# 06-_MCU_PORTA_B.net
KiCad netlist of a schematic drawn in Altium Designer
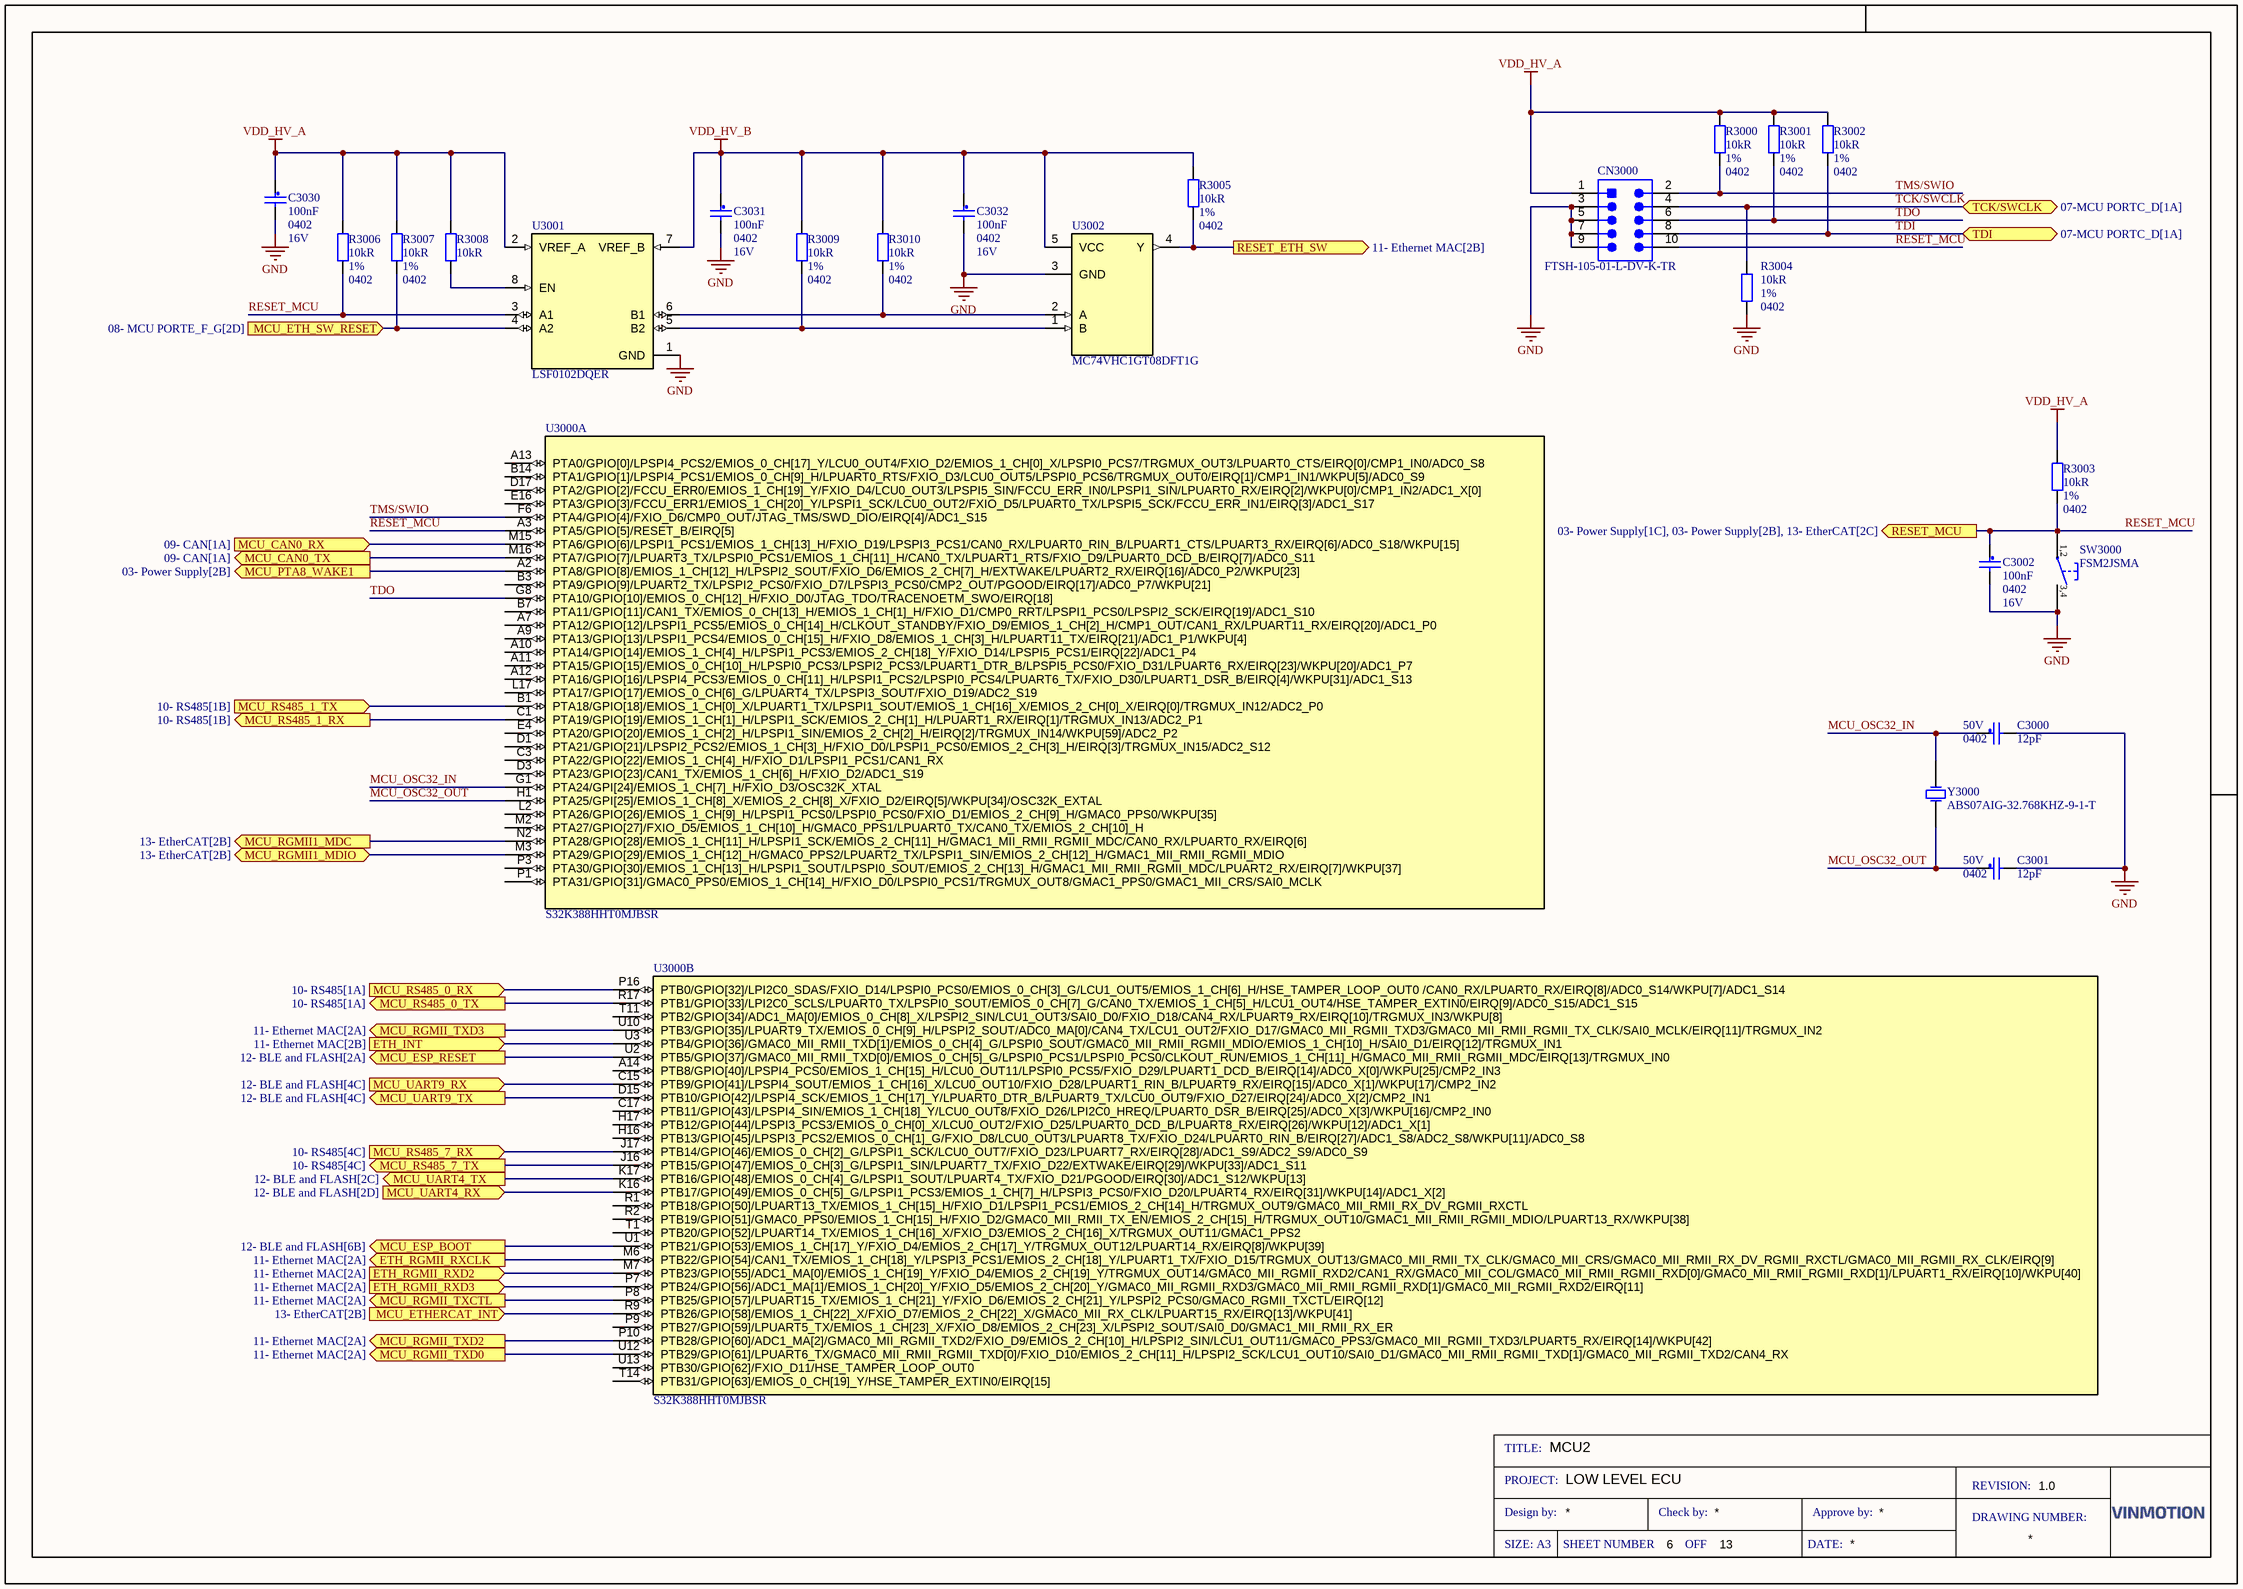
[diagram p0: 06- MCU PORTA_B.SchDoc]

(export (version "E")
  (design (tool "Eeschema 10.0.6"))
  (components
    (comp (ref "C3000")
      (value "GCM1555C1H120JA16D")
      (footprint "CAP0402")
      (description "CAP CER 12PF 50V C0G/NP0 0402")
      (fields
        (field (name "TOLERANCE") "5%")
        (field (name "VOLTAGE RATING") "50V")
        (field (name "CASE/PACKAGE") "0402")
        (field (name "CAPACITANCE") "12pF")
      )
      (libsource (lib "VMO_Lib") (part "CMP-00203-1"))
    )
    (comp (ref "C3001")
      (value "GCM1555C1H120JA16D")
      (footprint "CAP0402")
      (description "CAP CER 12PF 50V C0G/NP0 0402")
      (fields
        (field (name "TOLERANCE") "5%")
        (field (name "VOLTAGE RATING") "50V")
        (field (name "CASE/PACKAGE") "0402")
        (field (name "CAPACITANCE") "12pF")
      )
      (libsource (lib "VMO_Lib") (part "CMP-00203-1"))
    )
    (comp (ref "C3002")
      (value "0402YC104KAT2A")
      (footprint "CAP0402")
      (description "CAP CER 0.1UF 16V X7R 0402")
      (fields
        (field (name "CAPACITANCE") "100nF")
        (field (name "CASE/PACKAGE") "0402")
        (field (name "VOLTAGE RATING (DC)") "16V")
      )
      (libsource (lib "VMO_Lib") (part "CMP-00988-1"))
    )
    (comp (ref "C3030")
      (value "0402YC104KAT2A")
      (footprint "CAP0402")
      (description "CAP CER 0.1UF 16V X7R 0402")
      (fields
        (field (name "CAPACITANCE") "100nF")
        (field (name "CASE/PACKAGE") "0402")
        (field (name "VOLTAGE RATING (DC)") "16V")
      )
      (libsource (lib "VMO_Lib") (part "CMP-00988-1"))
    )
    (comp (ref "C3031")
      (value "0402YC104KAT2A")
      (footprint "CAP0402")
      (description "CAP CER 0.1UF 16V X7R 0402")
      (fields
        (field (name "CAPACITANCE") "100nF")
        (field (name "CASE/PACKAGE") "0402")
        (field (name "VOLTAGE RATING (DC)") "16V")
      )
      (libsource (lib "VMO_Lib") (part "CMP-00988-1"))
    )
    (comp (ref "C3032")
      (value "0402YC104KAT2A")
      (footprint "CAP0402")
      (description "CAP CER 0.1UF 16V X7R 0402")
      (fields
        (field (name "CAPACITANCE") "100nF")
        (field (name "CASE/PACKAGE") "0402")
        (field (name "VOLTAGE RATING (DC)") "16V")
      )
      (libsource (lib "VMO_Lib") (part "CMP-00988-1"))
    )
    (comp (ref "CN3000")
      (value "FTSH-105-01-L-DV-K-TR")
      (footprint "SMTC-FTSH-105-01-L-DV-K_R")
      (description "CONN HEADER SMD 10POS 1.27MM")
      (libsource (lib "VMO_Lib") (part "CMP-ROOT-0060-2"))
    )
    (comp (ref "R3000")
      (value "10kR")
      (footprint "RES0402")
      (description "RES 10K OHM 1% 1/16W 0402")
      (fields
        (field (name "MANUFACTURER") "Stackpole Electronics")
        (field (name "MANUFACTURER PART NUMBER") "RMCF0402FT10K0")
        (field (name "TOLERANCE") "1%")
        (field (name "CASE/PACKAGE") "0402")
      )
      (libsource (lib "VMO_Lib") (part "CMP-01105-1"))
    )
    (comp (ref "R3001")
      (value "10kR")
      (footprint "RES0402")
      (description "RES 10K OHM 1% 1/16W 0402")
      (fields
        (field (name "MANUFACTURER") "Stackpole Electronics")
        (field (name "MANUFACTURER PART NUMBER") "RMCF0402FT10K0")
        (field (name "TOLERANCE") "1%")
        (field (name "CASE/PACKAGE") "0402")
      )
      (libsource (lib "VMO_Lib") (part "CMP-01105-1"))
    )
    (comp (ref "R3002")
      (value "10kR")
      (footprint "RES0402")
      (description "RES 10K OHM 1% 1/16W 0402")
      (fields
        (field (name "MANUFACTURER") "Stackpole Electronics")
        (field (name "MANUFACTURER PART NUMBER") "RMCF0402FT10K0")
        (field (name "TOLERANCE") "1%")
        (field (name "CASE/PACKAGE") "0402")
      )
      (libsource (lib "VMO_Lib") (part "CMP-01105-1"))
    )
    (comp (ref "R3003")
      (value "10kR")
      (footprint "RES0402")
      (description "RES 10K OHM 1% 1/16W 0402")
      (fields
        (field (name "MANUFACTURER") "Stackpole Electronics")
        (field (name "MANUFACTURER PART NUMBER") "RMCF0402FT10K0")
        (field (name "TOLERANCE") "1%")
        (field (name "CASE/PACKAGE") "0402")
      )
      (libsource (lib "VMO_Lib") (part "CMP-01105-1"))
    )
    (comp (ref "R3004")
      (value "10kR")
      (footprint "RES0402")
      (description "RES 10K OHM 1% 1/16W 0402")
      (fields
        (field (name "MANUFACTURER") "Stackpole Electronics")
        (field (name "MANUFACTURER PART NUMBER") "RMCF0402FT10K0")
        (field (name "TOLERANCE") "1%")
        (field (name "CASE/PACKAGE") "0402")
      )
      (libsource (lib "VMO_Lib") (part "CMP-01105-1"))
    )
    (comp (ref "R3005")
      (value "10kR")
      (footprint "RES0402")
      (description "RES 10K OHM 1% 1/16W 0402")
      (fields
        (field (name "MANUFACTURER") "Stackpole Electronics")
        (field (name "MANUFACTURER PART NUMBER") "RMCF0402FT10K0")
        (field (name "TOLERANCE") "1%")
        (field (name "CASE/PACKAGE") "0402")
      )
      (libsource (lib "VMO_Lib") (part "CMP-01105-1"))
    )
    (comp (ref "R3006")
      (value "10kR")
      (footprint "RES0402")
      (description "RES 10K OHM 1% 1/16W 0402")
      (fields
        (field (name "MANUFACTURER") "Stackpole Electronics")
        (field (name "MANUFACTURER PART NUMBER") "RMCF0402FT10K0")
        (field (name "TOLERANCE") "1%")
        (field (name "CASE/PACKAGE") "0402")
      )
      (libsource (lib "VMO_Lib") (part "CMP-01105-1"))
    )
    (comp (ref "R3007")
      (value "10kR")
      (footprint "RES0402")
      (description "RES 10K OHM 1% 1/16W 0402")
      (fields
        (field (name "MANUFACTURER") "Stackpole Electronics")
        (field (name "MANUFACTURER PART NUMBER") "RMCF0402FT10K0")
        (field (name "TOLERANCE") "1%")
        (field (name "CASE/PACKAGE") "0402")
      )
      (libsource (lib "VMO_Lib") (part "CMP-01105-1"))
    )
    (comp (ref "R3008")
      (value "10kR")
      (footprint "RES0402")
      (description "RES 10K OHM 1% 1/16W 0402")
      (fields
        (field (name "MANUFACTURER") "Stackpole Electronics")
        (field (name "MANUFACTURER PART NUMBER") "RMCF0402FT10K0")
      )
      (libsource (lib "VMO_Lib") (part "CMP-01105-1"))
    )
    (comp (ref "R3009")
      (value "10kR")
      (footprint "RES0402")
      (description "RES 10K OHM 1% 1/16W 0402")
      (fields
        (field (name "MANUFACTURER") "Stackpole Electronics")
        (field (name "MANUFACTURER PART NUMBER") "RMCF0402FT10K0")
        (field (name "TOLERANCE") "1%")
        (field (name "CASE/PACKAGE") "0402")
      )
      (libsource (lib "VMO_Lib") (part "CMP-01105-1"))
    )
    (comp (ref "R3010")
      (value "10kR")
      (footprint "RES0402")
      (description "RES 10K OHM 1% 1/16W 0402")
      (fields
        (field (name "MANUFACTURER") "Stackpole Electronics")
        (field (name "MANUFACTURER PART NUMBER") "RMCF0402FT10K0")
        (field (name "TOLERANCE") "1%")
        (field (name "CASE/PACKAGE") "0402")
      )
      (libsource (lib "VMO_Lib") (part "CMP-01105-1"))
    )
    (comp (ref "SW3000")
      (value "FSM2JSMA")
      (footprint "TE_FSM2JSMASTR_R")
      (description "SWITCH TACTILE SPST-NO 0.05A 24V")
      (libsource (lib "VMO_Lib") (part "CMP-ROOT-0128-12"))
    )
    (comp (ref "U3000")
      (value "S32K388HHT0MJBSR")
      (footprint "BGA289C80P17X17_1400X1400X152")
      (fields (field (name "MANUFACTURER") "NXP Semiconductors"))
      (libsource (lib "VMO_Lib") (part "CMP-01150-1"))
    )
    (comp (ref "U3001")
      (value "LSF0102DQER")
      (footprint "8-XFDFN")
      (description "IC VOLTAGE LEVEL BIDIR 8-X2SON")
      (fields (field (name "MANUFACTURER") "Texas Instruments"))
      (libsource (lib "VMO_Lib") (part "CMP-01193-1"))
    )
    (comp (ref "U3002")
      (value "MC74VHC1GT08DFT1G")
      (footprint "SOT95P280X145-5N")
      (description "IC GATE AND 1CH 2-INP SC88A")
      (fields (field (name "MANUFACTURER") "onsemi"))
      (libsource (lib "VMO_Lib") (part "CMP-01194-1"))
    )
    (comp (ref "Y3000")
      (value "ABS07AIG-32.768KHZ-9-1-T")
      (footprint "CRYSTAL3215")
      (description "CRYSTAL 32.768KHZ 9PF SMD")
      (libsource (lib "VMO_Lib") (part "CMP-00382-1"))
    )
  )
  (nets
    (net (code "1") (name "/ETH_INT") (class "Default")
      (node (ref "U3000") (pin "U3") (pinfunction "PTB4/GPIO[36]/GMAC0_MII_RMII_TXD[1]/EMIOS_0_CH[4]_G/LPSPI0_SOUT/GMAC0_MII_RMII_RGMII_MDIO/EMIOS_1_CH[10]_H/SAI0_D1/EIRQ[12]/TRGMUX_IN1_U3") (pintype "bidirectional"))
    )
    (net (code "2") (name "/ETH_RGMII_RXCLK") (class "Default")
      (node (ref "U3000") (pin "M6") (pinfunction "PTB22/GPIO[54]/CAN1_TX/EMIOS_1_CH[18]_Y/LPSPI3_PCS1/EMIOS_2_CH[18]_Y/LPUART1_TX/FXIO_D15/TRGMUX_OUT13/GMAC0_MII_RMII_TX_CLK/GMAC0_MII_CRS/GMAC0_MII_RMII_RX_DV_RGMII_RXCTL/GMAC0_MII_RGMII_RX_CLK/EIRQ[9]_M6") (pintype "bidirectional"))
    )
    (net (code "3") (name "/ETH_RGMII_RXD2") (class "Default")
      (node (ref "U3000") (pin "M7") (pinfunction "PTB23/GPIO[55]/ADC1_MA[0]/EMIOS_1_CH[19]_Y/FXIO_D4/EMIOS_2_CH[19]_Y/TRGMUX_OUT14/GMAC0_MII_RGMII_RXD2/CAN1_RX/GMAC0_MII_COL/GMAC0_MII_RMII_RGMII_RXD[0]/GMAC0_MII_RMII_RGMII_RXD[1]/LPUART1_RX/EIRQ[10]/WKPU[40]_M7") (pintype "bidirectional"))
    )
    (net (code "4") (name "/ETH_RGMII_RXD3") (class "Default")
      (node (ref "U3000") (pin "P7") (pinfunction "PTB24/GPIO[56]/ADC1_MA[1]/EMIOS_1_CH[20]_Y/FXIO_D5/EMIOS_2_CH[20]_Y/GMAC0_MII_RGMII_RXD3/GMAC0_MII_RMII_RGMII_RXD[1]/GMAC0_MII_RGMII_RXD2/EIRQ[11]_P7") (pintype "bidirectional"))
    )
    (net (code "5") (name "/MCU_CAN0_RX") (class "Default")
      (node (ref "U3000") (pin "M15") (pinfunction "PTA6/GPIO[6]/LPSPI1_PCS1/EMIOS_1_CH[13]_H/FXIO_D19/LPSPI3_PCS1/CAN0_RX/LPUART0_RIN_B/LPUART1_CTS/LPUART3_RX/EIRQ[6]/ADC0_S18/WKPU[15]_M15") (pintype "bidirectional"))
    )
    (net (code "6") (name "/MCU_CAN0_TX") (class "Default")
      (node (ref "U3000") (pin "M16") (pinfunction "PTA7/GPIO[7]/LPUART3_TX/LPSPI0_PCS1/EMIOS_1_CH[11]_H/CAN0_TX/LPUART1_RTS/FXIO_D9/LPUART0_DCD_B/EIRQ[7]/ADC0_S11_M16") (pintype "bidirectional"))
    )
    (net (code "7") (name "/MCU_ESP_BOOT") (class "Default")
      (node (ref "U3000") (pin "U1") (pinfunction "PTB21/GPIO[53]/EMIOS_1_CH[17]_Y/FXIO_D4/EMIOS_2_CH[17]_Y/TRGMUX_OUT12/LPUART14_RX/EIRQ[8]/WKPU[39]_U1") (pintype "bidirectional"))
    )
    (net (code "8") (name "/MCU_ESP_RESET") (class "Default")
      (node (ref "U3000") (pin "U2") (pinfunction "PTB5/GPIO[37]/GMAC0_MII_RMII_TXD[0]/EMIOS_0_CH[5]_G/LPSPI0_PCS1/LPSPI0_PCS0/CLKOUT_RUN/EMIOS_1_CH[11]_H/GMAC0_MII_RMII_RGMII_MDC/EIRQ[13]/TRGMUX_IN0_U2") (pintype "bidirectional"))
    )
    (net (code "9") (name "/MCU_ETHERCAT_INT") (class "Default")
      (node (ref "U3000") (pin "R9") (pinfunction "PTB26/GPIO[58]/EMIOS_1_CH[22]_X/FXIO_D7/EMIOS_2_CH[22]_X/GMAC0_MII_RX_CLK/LPUART15_RX/EIRQ[13]/WKPU[41]_R9") (pintype "bidirectional"))
    )
    (net (code "10") (name "/MCU_ETH_SW_RESET") (class "Default")
      (node (ref "R3007") (pin "1") (pinfunction "1_1") (pintype "passive"))
      (node (ref "U3001") (pin "4") (pinfunction "A2_4") (pintype "bidirectional"))
    )
    (net (code "11") (name "/MCU_OSC32_IN") (class "Default")
      (node (ref "C3000") (pin "1") (pinfunction "1_1") (pintype "passive"))
      (node (ref "U3000") (pin "G1") (pinfunction "PTA24/GPI[24]/EMIOS_1_CH[7]_H/FXIO_D3/OSC32K_XTAL_G1") (pintype "bidirectional"))
      (node (ref "Y3000") (pin "2") (pinfunction "OSC2_2") (pintype "passive"))
    )
    (net (code "12") (name "/MCU_OSC32_OUT") (class "Default")
      (node (ref "C3001") (pin "1") (pinfunction "1_1") (pintype "passive"))
      (node (ref "U3000") (pin "H1") (pinfunction "PTA25/GPI[25]/EMIOS_1_CH[8]_X/EMIOS_2_CH[8]_X/FXIO_D2/EIRQ[5]/WKPU[34]/OSC32K_EXTAL_H1") (pintype "bidirectional"))
      (node (ref "Y3000") (pin "1") (pinfunction "OSC1_1") (pintype "passive"))
    )
    (net (code "13") (name "/MCU_PTA8_WAKE1") (class "Default")
      (node (ref "U3000") (pin "A2") (pinfunction "PTA8/GPIO[8]/EMIOS_1_CH[12]_H/LPSPI2_SOUT/FXIO_D6/EMIOS_2_CH[7]_H/EXTWAKE/LPUART2_RX/EIRQ[16]/ADC0_P2/WKPU[23]_A2") (pintype "bidirectional"))
    )
    (net (code "14") (name "/MCU_RGMII1_MDC") (class "Default")
      (node (ref "U3000") (pin "N2") (pinfunction "PTA28/GPIO[28]/EMIOS_1_CH[11]_H/LPSPI1_SCK/EMIOS_2_CH[11]_H/GMAC1_MII_RMII_RGMII_MDC/CAN0_RX/LPUART0_RX/EIRQ[6]_N2") (pintype "bidirectional"))
    )
    (net (code "15") (name "/MCU_RGMII1_MDIO") (class "Default")
      (node (ref "U3000") (pin "M3") (pinfunction "PTA29/GPIO[29]/EMIOS_1_CH[12]_H/GMAC0_PPS2/LPUART2_TX/LPSPI1_SIN/EMIOS_2_CH[12]_H/GMAC1_MII_RMII_RGMII_MDIO_M3") (pintype "bidirectional"))
    )
    (net (code "16") (name "/MCU_RGMII_TXCTL") (class "Default")
      (node (ref "U3000") (pin "P8") (pinfunction "PTB25/GPIO[57]/LPUART15_TX/EMIOS_1_CH[21]_Y/FXIO_D6/EMIOS_2_CH[21]_Y/LPSPI2_PCS0/GMAC0_RGMII_TXCTL/EIRQ[12]_P8") (pintype "bidirectional"))
    )
    (net (code "17") (name "/MCU_RGMII_TXD0") (class "Default")
      (node (ref "U3000") (pin "U12") (pinfunction "PTB29/GPIO[61]/LPUART6_TX/GMAC0_MII_RMII_RGMII_TXD[0]/FXIO_D10/EMIOS_2_CH[11]_H/LPSPI2_SCK/LCU1_OUT10/SAI0_D1/GMAC0_MII_RMII_RGMII_TXD[1]/GMAC0_MII_RGMII_TXD2/CAN4_RX_U12") (pintype "bidirectional"))
    )
    (net (code "18") (name "/MCU_RGMII_TXD2") (class "Default")
      (node (ref "U3000") (pin "P10") (pinfunction "PTB28/GPIO[60]/ADC1_MA[2]/GMAC0_MII_RGMII_TXD2/FXIO_D9/EMIOS_2_CH[10]_H/LPSPI2_SIN/LCU1_OUT11/GMAC0_PPS3/GMAC0_MII_RGMII_TXD3/LPUART5_RX/EIRQ[14]/WKPU[42]_P10") (pintype "bidirectional"))
    )
    (net (code "19") (name "/MCU_RGMII_TXD3") (class "Default")
      (node (ref "U3000") (pin "U10") (pinfunction "PTB3/GPIO[35]/LPUART9_TX/EMIOS_0_CH[9]_H/LPSPI2_SOUT/ADC0_MA[0]/CAN4_TX/LCU1_OUT2/FXIO_D17/GMAC0_MII_RGMII_TXD3/GMAC0_MII_RMII_RGMII_TX_CLK/SAI0_MCLK/EIRQ[11]/TRGMUX_IN2_U10") (pintype "bidirectional"))
    )
    (net (code "20") (name "/MCU_RS485_0_RX") (class "Default")
      (node (ref "U3000") (pin "P16") (pinfunction "PTB0/GPIO[32]/LPI2C0_SDAS/FXIO_D14/LPSPI0_PCS0/EMIOS_0_CH[3]_G/LCU1_OUT5/EMIOS_1_CH[6]_H/HSE_TAMPER_LOOP_OUT0_/CAN0_RX/LPUART0_RX/EIRQ[8]/ADC0_S14/WKPU[7]/ADC1_S14_P16") (pintype "bidirectional"))
    )
    (net (code "21") (name "/MCU_RS485_0_TX") (class "Default")
      (node (ref "U3000") (pin "R17") (pinfunction "PTB1/GPIO[33]/LPI2C0_SCLS/LPUART0_TX/LPSPI0_SOUT/EMIOS_0_CH[7]_G/CAN0_TX/EMIOS_1_CH[5]_H/LCU1_OUT4/HSE_TAMPER_EXTIN0/EIRQ[9]/ADC0_S15/ADC1_S15_R17") (pintype "bidirectional"))
    )
    (net (code "22") (name "/MCU_RS485_1_RX") (class "Default")
      (node (ref "U3000") (pin "C1") (pinfunction "PTA19/GPIO[19]/EMIOS_1_CH[1]_H/LPSPI1_SCK/EMIOS_2_CH[1]_H/LPUART1_RX/EIRQ[1]/TRGMUX_IN13/ADC2_P1_C1") (pintype "bidirectional"))
    )
    (net (code "23") (name "/MCU_RS485_1_TX") (class "Default")
      (node (ref "U3000") (pin "B1") (pinfunction "PTA18/GPIO[18]/EMIOS_1_CH[0]_X/LPUART1_TX/LPSPI1_SOUT/EMIOS_1_CH[16]_X/EMIOS_2_CH[0]_X/EIRQ[0]/TRGMUX_IN12/ADC2_P0_B1") (pintype "bidirectional"))
    )
    (net (code "24") (name "/MCU_RS485_7_RX") (class "Default")
      (node (ref "U3000") (pin "J17") (pinfunction "PTB14/GPIO[46]/EMIOS_0_CH[2]_G/LPSPI1_SCK/LCU0_OUT7/FXIO_D23/LPUART7_RX/EIRQ[28]/ADC1_S9/ADC2_S9/ADC0_S9_J17") (pintype "bidirectional"))
    )
    (net (code "25") (name "/MCU_RS485_7_TX") (class "Default")
      (node (ref "U3000") (pin "J16") (pinfunction "PTB15/GPIO[47]/EMIOS_0_CH[3]_G/LPSPI1_SIN/LPUART7_TX/FXIO_D22/EXTWAKE/EIRQ[29]/WKPU[33]/ADC1_S11_J16") (pintype "bidirectional"))
    )
    (net (code "26") (name "/MCU_UART4_RX") (class "Default")
      (node (ref "U3000") (pin "K16") (pinfunction "PTB17/GPIO[49]/EMIOS_0_CH[5]_G/LPSPI1_PCS3/EMIOS_1_CH[7]_H/LPSPI3_PCS0/FXIO_D20/LPUART4_RX/EIRQ[31]/WKPU[14]/ADC1_X[2]_K16") (pintype "bidirectional"))
    )
    (net (code "27") (name "/MCU_UART4_TX") (class "Default")
      (node (ref "U3000") (pin "K17") (pinfunction "PTB16/GPIO[48]/EMIOS_0_CH[4]_G/LPSPI1_SOUT/LPUART4_TX/FXIO_D21/PGOOD/EIRQ[30]/ADC1_S12/WKPU[13]_K17") (pintype "bidirectional"))
    )
    (net (code "28") (name "/MCU_UART9_RX") (class "Default")
      (node (ref "U3000") (pin "C15") (pinfunction "PTB9/GPIO[41]/LPSPI4_SOUT/EMIOS_1_CH[16]_X/LCU0_OUT10/FXIO_D28/LPUART1_RIN_B/LPUART9_RX/EIRQ[15]/ADC0_X[1]/WKPU[17]/CMP2_IN2_C15") (pintype "bidirectional"))
    )
    (net (code "29") (name "/MCU_UART9_TX") (class "Default")
      (node (ref "U3000") (pin "D15") (pinfunction "PTB10/GPIO[42]/LPSPI4_SCK/EMIOS_1_CH[17]_Y/LPUART0_DTR_B/LPUART9_TX/LCU0_OUT9/FXIO_D27/EIRQ[24]/ADC0_X[2]/CMP2_IN1_D15") (pintype "bidirectional"))
    )
    (net (code "30") (name "/RESET_ETH_SW") (class "Default")
      (node (ref "R3005") (pin "1") (pinfunction "1_1") (pintype "passive"))
      (node (ref "U3002") (pin "4") (pinfunction "Y_4") (pintype "output"))
    )
    (net (code "31") (name "/RESET_MCU") (class "Default")
      (node (ref "C3002") (pin "1") (pinfunction "1_1") (pintype "passive"))
      (node (ref "CN3000") (pin "10") (pinfunction "10_10") (pintype "passive"))
      (node (ref "R3003") (pin "1") (pinfunction "1_1") (pintype "passive"))
      (node (ref "R3006") (pin "1") (pinfunction "1_1") (pintype "passive"))
      (node (ref "SW3000") (pin "1") (pinfunction "1_1") (pintype "passive"))
      (node (ref "SW3000") (pin "2") (pinfunction "2_2") (pintype "passive"))
      (node (ref "U3000") (pin "A3") (pinfunction "PTA5/GPIO[5]/RESET_B/EIRQ[5]_A3") (pintype "bidirectional"))
      (node (ref "U3001") (pin "3") (pinfunction "A1_3") (pintype "bidirectional"))
    )
    (net (code "32") (name "/TCK{slash}SWCLK") (class "Default")
      (node (ref "CN3000") (pin "4") (pinfunction "4_4") (pintype "passive"))
      (node (ref "R3004") (pin "2") (pinfunction "2_2") (pintype "passive"))
    )
    (net (code "33") (name "/TDI") (class "Default")
      (node (ref "CN3000") (pin "8") (pinfunction "8_8") (pintype "passive"))
      (node (ref "R3002") (pin "1") (pinfunction "1_1") (pintype "passive"))
    )
    (net (code "34") (name "/TDO") (class "Default")
      (node (ref "CN3000") (pin "6") (pinfunction "6_6") (pintype "passive"))
      (node (ref "R3001") (pin "1") (pinfunction "1_1") (pintype "passive"))
      (node (ref "U3000") (pin "G8") (pinfunction "PTA10/GPIO[10]/EMIOS_0_CH[12]_H/FXIO_D0/JTAG_TDO/TRACENOETM_SWO/EIRQ[18]_G8") (pintype "bidirectional"))
    )
    (net (code "35") (name "/TMS{slash}SWIO") (class "Default")
      (node (ref "CN3000") (pin "2") (pinfunction "2_2") (pintype "passive"))
      (node (ref "R3000") (pin "1") (pinfunction "1_1") (pintype "passive"))
      (node (ref "U3000") (pin "F6") (pinfunction "PTA4/GPIO[4]/FXIO_D6/CMP0_OUT/JTAG_TMS/SWD_DIO/EIRQ[4]/ADC1_S15_F6") (pintype "bidirectional"))
    )
    (net (code "36") (name "GND") (class "Default")
      (node (ref "C3000") (pin "2") (pinfunction "2_2") (pintype "passive"))
      (node (ref "C3001") (pin "2") (pinfunction "2_2") (pintype "passive"))
      (node (ref "C3002") (pin "2") (pinfunction "2_2") (pintype "passive"))
      (node (ref "C3030") (pin "2") (pinfunction "2_2") (pintype "passive"))
      (node (ref "C3031") (pin "2") (pinfunction "2_2") (pintype "passive"))
      (node (ref "C3032") (pin "2") (pinfunction "2_2") (pintype "passive"))
      (node (ref "CN3000") (pin "3") (pinfunction "3_3") (pintype "passive"))
      (node (ref "CN3000") (pin "5") (pinfunction "5_5") (pintype "passive"))
      (node (ref "CN3000") (pin "7") (pinfunction "7_7") (pintype "passive"))
      (node (ref "CN3000") (pin "9") (pinfunction "9_9") (pintype "passive"))
      (node (ref "R3004") (pin "1") (pinfunction "1_1") (pintype "passive"))
      (node (ref "SW3000") (pin "3") (pinfunction "3_3") (pintype "passive"))
      (node (ref "SW3000") (pin "4") (pinfunction "4_4") (pintype "passive"))
      (node (ref "U3001") (pin "1") (pinfunction "GND_1") (pintype "power_in"))
      (node (ref "U3002") (pin "3") (pinfunction "GND_3") (pintype "passive"))
    )
    (net (code "37") (name "Net-(U3001-B1)") (class "Default")
      (node (ref "R3010") (pin "1") (pinfunction "1_1") (pintype "passive"))
      (node (ref "U3001") (pin "6") (pinfunction "B1_6") (pintype "bidirectional"))
      (node (ref "U3002") (pin "2") (pinfunction "A_2") (pintype "input"))
    )
    (net (code "38") (name "Net-(U3001-B2)") (class "Default")
      (node (ref "R3009") (pin "1") (pinfunction "1_1") (pintype "passive"))
      (node (ref "U3001") (pin "5") (pinfunction "B2_5") (pintype "bidirectional"))
      (node (ref "U3002") (pin "1") (pinfunction "B_1") (pintype "input"))
    )
    (net (code "39") (name "Net-(U3001-EN)") (class "Default")
      (node (ref "R3008") (pin "1") (pinfunction "1_1") (pintype "passive"))
      (node (ref "U3001") (pin "8") (pinfunction "EN_8") (pintype "input"))
    )
    (net (code "40") (name "VDD_HV_A") (class "Default")
      (node (ref "C3030") (pin "1") (pinfunction "1_1") (pintype "passive"))
      (node (ref "CN3000") (pin "1") (pinfunction "1_1") (pintype "passive"))
      (node (ref "R3000") (pin "2") (pinfunction "2_2") (pintype "passive"))
      (node (ref "R3001") (pin "2") (pinfunction "2_2") (pintype "passive"))
      (node (ref "R3002") (pin "2") (pinfunction "2_2") (pintype "passive"))
      (node (ref "R3003") (pin "2") (pinfunction "2_2") (pintype "passive"))
      (node (ref "R3006") (pin "2") (pinfunction "2_2") (pintype "passive"))
      (node (ref "R3007") (pin "2") (pinfunction "2_2") (pintype "passive"))
      (node (ref "R3008") (pin "2") (pinfunction "2_2") (pintype "passive"))
      (node (ref "U3001") (pin "2") (pinfunction "VREF_A_2") (pintype "input"))
    )
    (net (code "41") (name "VDD_HV_B") (class "Default")
      (node (ref "C3031") (pin "1") (pinfunction "1_1") (pintype "passive"))
      (node (ref "C3032") (pin "1") (pinfunction "1_1") (pintype "passive"))
      (node (ref "R3005") (pin "2") (pinfunction "2_2") (pintype "passive"))
      (node (ref "R3009") (pin "2") (pinfunction "2_2") (pintype "passive"))
      (node (ref "R3010") (pin "2") (pinfunction "2_2") (pintype "passive"))
      (node (ref "U3001") (pin "7") (pinfunction "VREF_B_7") (pintype "input"))
      (node (ref "U3002") (pin "5") (pinfunction "VCC_5") (pintype "passive"))
    )
    (net (code "42") (name "unconnected-(U3000A-PTA0{slash}GPIO[0]{slash}LPSPI4_PCS2{slash}EMIOS_0_CH[17]_Y{slash}LCU0_OUT4{slash}FXIO_D2{slash}EMIOS_1_CH[0]_X{slash}LPSPI0_PCS7{slash}TRGMUX_OUT3{slash}LPUART0_CTS{slash}EIRQ[0]{slash}CMP1_IN0{slash}ADC0_S8-PadA13)") (class "Default")
      (node (ref "U3000") (pin "A13") (pinfunction "PTA0/GPIO[0]/LPSPI4_PCS2/EMIOS_0_CH[17]_Y/LCU0_OUT4/FXIO_D2/EMIOS_1_CH[0]_X/LPSPI0_PCS7/TRGMUX_OUT3/LPUART0_CTS/EIRQ[0]/CMP1_IN0/ADC0_S8_A13") (pintype "bidirectional"))
    )
    (net (code "43") (name "unconnected-(U3000A-PTA1{slash}GPIO[1]{slash}LPSPI4_PCS1{slash}EMIOS_0_CH[9]_H{slash}LPUART0_RTS{slash}FXIO_D3{slash}LCU0_OUT5{slash}LPSPI0_PCS6{slash}TRGMUX_OUT0{slash}EIRQ[1]{slash}CMP1_IN1{slash}WKPU[5]{slash}ADC0_S9-PadB14)") (class "Default")
      (node (ref "U3000") (pin "B14") (pinfunction "PTA1/GPIO[1]/LPSPI4_PCS1/EMIOS_0_CH[9]_H/LPUART0_RTS/FXIO_D3/LCU0_OUT5/LPSPI0_PCS6/TRGMUX_OUT0/EIRQ[1]/CMP1_IN1/WKPU[5]/ADC0_S9_B14") (pintype "bidirectional"))
    )
    (net (code "44") (name "unconnected-(U3000A-PTA2{slash}GPIO[2]{slash}FCCU_ERR0{slash}EMIOS_1_CH[19]_Y{slash}FXIO_D4{slash}LCU0_OUT3{slash}LPSPI5_SIN{slash}FCCU_ERR_IN0{slash}LPSPI1_SIN{slash}LPUART0_RX{slash}EIRQ[2]{slash}WKPU[0]{slash}CMP1_IN2{slash}ADC1_X[0]-PadD17)") (class "Default")
      (node (ref "U3000") (pin "D17") (pinfunction "PTA2/GPIO[2]/FCCU_ERR0/EMIOS_1_CH[19]_Y/FXIO_D4/LCU0_OUT3/LPSPI5_SIN/FCCU_ERR_IN0/LPSPI1_SIN/LPUART0_RX/EIRQ[2]/WKPU[0]/CMP1_IN2/ADC1_X[0]_D17") (pintype "bidirectional"))
    )
    (net (code "45") (name "unconnected-(U3000A-PTA3{slash}GPIO[3]{slash}FCCU_ERR1{slash}EMIOS_1_CH[20]_Y{slash}LPSPI1_SCK{slash}LCU0_OUT2{slash}FXIO_D5{slash}LPUART0_TX{slash}LPSPI5_SCK{slash}FCCU_ERR_IN1{slash}EIRQ[3]{slash}ADC1_S17-PadE16)") (class "Default")
      (node (ref "U3000") (pin "E16") (pinfunction "PTA3/GPIO[3]/FCCU_ERR1/EMIOS_1_CH[20]_Y/LPSPI1_SCK/LCU0_OUT2/FXIO_D5/LPUART0_TX/LPSPI5_SCK/FCCU_ERR_IN1/EIRQ[3]/ADC1_S17_E16") (pintype "bidirectional"))
    )
    (net (code "46") (name "unconnected-(U3000A-PTA9{slash}GPIO[9]{slash}LPUART2_TX{slash}LPSPI2_PCS0{slash}FXIO_D7{slash}LPSPI3_PCS0{slash}CMP2_OUT{slash}PGOOD{slash}EIRQ[17]{slash}ADC0_P7{slash}WKPU[21]-PadB3)") (class "Default")
      (node (ref "U3000") (pin "B3") (pinfunction "PTA9/GPIO[9]/LPUART2_TX/LPSPI2_PCS0/FXIO_D7/LPSPI3_PCS0/CMP2_OUT/PGOOD/EIRQ[17]/ADC0_P7/WKPU[21]_B3") (pintype "bidirectional"))
    )
    (net (code "47") (name "unconnected-(U3000A-PTA11{slash}GPIO[11]{slash}CAN1_TX{slash}EMIOS_0_CH[13]_H{slash}EMIOS_1_CH[1]_H{slash}FXIO_D1{slash}CMP0_RRT{slash}LPSPI1_PCS0{slash}LPSPI2_SCK{slash}EIRQ[19]{slash}ADC1_S10-PadB7)") (class "Default")
      (node (ref "U3000") (pin "B7") (pinfunction "PTA11/GPIO[11]/CAN1_TX/EMIOS_0_CH[13]_H/EMIOS_1_CH[1]_H/FXIO_D1/CMP0_RRT/LPSPI1_PCS0/LPSPI2_SCK/EIRQ[19]/ADC1_S10_B7") (pintype "bidirectional"))
    )
    (net (code "48") (name "unconnected-(U3000A-PTA12{slash}GPIO[12]{slash}LPSPI1_PCS5{slash}EMIOS_0_CH[14]_H{slash}CLKOUT_STANDBY{slash}FXIO_D9{slash}EMIOS_1_CH[2]_H{slash}CMP1_OUT{slash}CAN1_RX{slash}LPUART11_RX{slash}EIRQ[20]{slash}ADC1_P0-PadA7)") (class "Default")
      (node (ref "U3000") (pin "A7") (pinfunction "PTA12/GPIO[12]/LPSPI1_PCS5/EMIOS_0_CH[14]_H/CLKOUT_STANDBY/FXIO_D9/EMIOS_1_CH[2]_H/CMP1_OUT/CAN1_RX/LPUART11_RX/EIRQ[20]/ADC1_P0_A7") (pintype "bidirectional"))
    )
    (net (code "49") (name "unconnected-(U3000A-PTA13{slash}GPIO[13]{slash}LPSPI1_PCS4{slash}EMIOS_0_CH[15]_H{slash}FXIO_D8{slash}EMIOS_1_CH[3]_H{slash}LPUART11_TX{slash}EIRQ[21]{slash}ADC1_P1{slash}WKPU[4]-PadA9)") (class "Default")
      (node (ref "U3000") (pin "A9") (pinfunction "PTA13/GPIO[13]/LPSPI1_PCS4/EMIOS_0_CH[15]_H/FXIO_D8/EMIOS_1_CH[3]_H/LPUART11_TX/EIRQ[21]/ADC1_P1/WKPU[4]_A9") (pintype "bidirectional"))
    )
    (net (code "50") (name "unconnected-(U3000A-PTA14{slash}GPIO[14]{slash}EMIOS_1_CH[4]_H{slash}LPSPI1_PCS3{slash}EMIOS_2_CH[18]_Y{slash}FXIO_D14{slash}LPSPI5_PCS1{slash}EIRQ[22]{slash}ADC1_P4-PadA10)") (class "Default")
      (node (ref "U3000") (pin "A10") (pinfunction "PTA14/GPIO[14]/EMIOS_1_CH[4]_H/LPSPI1_PCS3/EMIOS_2_CH[18]_Y/FXIO_D14/LPSPI5_PCS1/EIRQ[22]/ADC1_P4_A10") (pintype "bidirectional"))
    )
    (net (code "51") (name "unconnected-(U3000A-PTA15{slash}GPIO[15]{slash}EMIOS_0_CH[10]_H{slash}LPSPI0_PCS3{slash}LPSPI2_PCS3{slash}LPUART1_DTR_B{slash}LPSPI5_PCS0{slash}FXIO_D31{slash}LPUART6_RX{slash}EIRQ[23]{slash}WKPU[20]{slash}ADC1_P7-PadA11)") (class "Default")
      (node (ref "U3000") (pin "A11") (pinfunction "PTA15/GPIO[15]/EMIOS_0_CH[10]_H/LPSPI0_PCS3/LPSPI2_PCS3/LPUART1_DTR_B/LPSPI5_PCS0/FXIO_D31/LPUART6_RX/EIRQ[23]/WKPU[20]/ADC1_P7_A11") (pintype "bidirectional"))
    )
    (net (code "52") (name "unconnected-(U3000A-PTA16{slash}GPIO[16]{slash}LPSPI4_PCS3{slash}EMIOS_0_CH[11]_H{slash}LPSPI1_PCS2{slash}LPSPI0_PCS4{slash}LPUART6_TX{slash}FXIO_D30{slash}LPUART1_DSR_B{slash}EIRQ[4]{slash}WKPU[31]{slash}ADC1_S13-PadA12)") (class "Default")
      (node (ref "U3000") (pin "A12") (pinfunction "PTA16/GPIO[16]/LPSPI4_PCS3/EMIOS_0_CH[11]_H/LPSPI1_PCS2/LPSPI0_PCS4/LPUART6_TX/FXIO_D30/LPUART1_DSR_B/EIRQ[4]/WKPU[31]/ADC1_S13_A12") (pintype "bidirectional"))
    )
    (net (code "53") (name "unconnected-(U3000A-PTA17{slash}GPIO[17]{slash}EMIOS_0_CH[6]_G{slash}LPUART4_TX{slash}LPSPI3_SOUT{slash}FXIO_D19{slash}ADC2_S19-PadL17)") (class "Default")
      (node (ref "U3000") (pin "L17") (pinfunction "PTA17/GPIO[17]/EMIOS_0_CH[6]_G/LPUART4_TX/LPSPI3_SOUT/FXIO_D19/ADC2_S19_L17") (pintype "bidirectional"))
    )
    (net (code "54") (name "unconnected-(U3000A-PTA20{slash}GPIO[20]{slash}EMIOS_1_CH[2]_H{slash}LPSPI1_SIN{slash}EMIOS_2_CH[2]_H{slash}EIRQ[2]{slash}TRGMUX_IN14{slash}WKPU[59]{slash}ADC2_P2-PadE4)") (class "Default")
      (node (ref "U3000") (pin "E4") (pinfunction "PTA20/GPIO[20]/EMIOS_1_CH[2]_H/LPSPI1_SIN/EMIOS_2_CH[2]_H/EIRQ[2]/TRGMUX_IN14/WKPU[59]/ADC2_P2_E4") (pintype "bidirectional"))
    )
    (net (code "55") (name "unconnected-(U3000A-PTA21{slash}GPIO[21]{slash}LPSPI2_PCS2{slash}EMIOS_1_CH[3]_H{slash}FXIO_D0{slash}LPSPI1_PCS0{slash}EMIOS_2_CH[3]_H{slash}EIRQ[3]{slash}TRGMUX_IN15{slash}ADC2_S12-PadD1)") (class "Default")
      (node (ref "U3000") (pin "D1") (pinfunction "PTA21/GPIO[21]/LPSPI2_PCS2/EMIOS_1_CH[3]_H/FXIO_D0/LPSPI1_PCS0/EMIOS_2_CH[3]_H/EIRQ[3]/TRGMUX_IN15/ADC2_S12_D1") (pintype "bidirectional"))
    )
    (net (code "56") (name "unconnected-(U3000A-PTA22{slash}GPIO[22]{slash}EMIOS_1_CH[4]_H{slash}FXIO_D1{slash}LPSPI1_PCS1{slash}CAN1_RX-PadC3)") (class "Default")
      (node (ref "U3000") (pin "C3") (pinfunction "PTA22/GPIO[22]/EMIOS_1_CH[4]_H/FXIO_D1/LPSPI1_PCS1/CAN1_RX_C3") (pintype "bidirectional"))
    )
    (net (code "57") (name "unconnected-(U3000A-PTA23{slash}GPIO[23]{slash}CAN1_TX{slash}EMIOS_1_CH[6]_H{slash}FXIO_D2{slash}ADC1_S19-PadD3)") (class "Default")
      (node (ref "U3000") (pin "D3") (pinfunction "PTA23/GPIO[23]/CAN1_TX/EMIOS_1_CH[6]_H/FXIO_D2/ADC1_S19_D3") (pintype "bidirectional"))
    )
    (net (code "58") (name "unconnected-(U3000A-PTA26{slash}GPIO[26]{slash}EMIOS_1_CH[9]_H{slash}LPSPI1_PCS0{slash}LPSPI0_PCS0{slash}FXIO_D1{slash}EMIOS_2_CH[9]_H{slash}GMAC0_PPS0{slash}WKPU[35]-PadL2)") (class "Default")
      (node (ref "U3000") (pin "L2") (pinfunction "PTA26/GPIO[26]/EMIOS_1_CH[9]_H/LPSPI1_PCS0/LPSPI0_PCS0/FXIO_D1/EMIOS_2_CH[9]_H/GMAC0_PPS0/WKPU[35]_L2") (pintype "bidirectional"))
    )
    (net (code "59") (name "unconnected-(U3000A-PTA27{slash}GPIO[27]{slash}FXIO_D5{slash}EMIOS_1_CH[10]_H{slash}GMAC0_PPS1{slash}LPUART0_TX{slash}CAN0_TX{slash}EMIOS_2_CH[10]_H-PadM2)") (class "Default")
      (node (ref "U3000") (pin "M2") (pinfunction "PTA27/GPIO[27]/FXIO_D5/EMIOS_1_CH[10]_H/GMAC0_PPS1/LPUART0_TX/CAN0_TX/EMIOS_2_CH[10]_H_M2") (pintype "bidirectional"))
    )
    (net (code "60") (name "unconnected-(U3000A-PTA30{slash}GPIO[30]{slash}EMIOS_1_CH[13]_H{slash}LPSPI1_SOUT{slash}LPSPI0_SOUT{slash}EMIOS_2_CH[13]_H{slash}GMAC1_MII_RMII_RGMII_MDC{slash}LPUART2_RX{slash}EIRQ[7]{slash}WKPU[37]-PadP3)") (class "Default")
      (node (ref "U3000") (pin "P3") (pinfunction "PTA30/GPIO[30]/EMIOS_1_CH[13]_H/LPSPI1_SOUT/LPSPI0_SOUT/EMIOS_2_CH[13]_H/GMAC1_MII_RMII_RGMII_MDC/LPUART2_RX/EIRQ[7]/WKPU[37]_P3") (pintype "bidirectional"))
    )
    (net (code "61") (name "unconnected-(U3000A-PTA31{slash}GPIO[31]{slash}GMAC0_PPS0{slash}EMIOS_1_CH[14]_H{slash}FXIO_D0{slash}LPSPI0_PCS1{slash}TRGMUX_OUT8{slash}GMAC1_PPS0{slash}GMAC1_MII_CRS{slash}SAI0_MCLK-PadP1)") (class "Default")
      (node (ref "U3000") (pin "P1") (pinfunction "PTA31/GPIO[31]/GMAC0_PPS0/EMIOS_1_CH[14]_H/FXIO_D0/LPSPI0_PCS1/TRGMUX_OUT8/GMAC1_PPS0/GMAC1_MII_CRS/SAI0_MCLK_P1") (pintype "bidirectional"))
    )
    (net (code "62") (name "unconnected-(U3000B-PTB2{slash}GPIO[34]{slash}ADC1_MA[0]{slash}EMIOS_0_CH[8]_X{slash}LPSPI2_SIN{slash}LCU1_OUT3{slash}SAI0_D0{slash}FXIO_D18{slash}CAN4_RX{slash}LPUART9_RX{slash}EIRQ[10]{slash}TRGMUX_IN3{slash}WKPU[8]-PadT11)") (class "Default")
      (node (ref "U3000") (pin "T11") (pinfunction "PTB2/GPIO[34]/ADC1_MA[0]/EMIOS_0_CH[8]_X/LPSPI2_SIN/LCU1_OUT3/SAI0_D0/FXIO_D18/CAN4_RX/LPUART9_RX/EIRQ[10]/TRGMUX_IN3/WKPU[8]_T11") (pintype "bidirectional"))
    )
    (net (code "63") (name "unconnected-(U3000B-PTB8{slash}GPIO[40]{slash}LPSPI4_PCS0{slash}EMIOS_1_CH[15]_H{slash}LCU0_OUT11{slash}LPSPI0_PCS5{slash}FXIO_D29{slash}LPUART1_DCD_B{slash}EIRQ[14]{slash}ADC0_X[0]{slash}WKPU[25]{slash}CMP2_IN3-PadA14)") (class "Default")
      (node (ref "U3000") (pin "A14") (pinfunction "PTB8/GPIO[40]/LPSPI4_PCS0/EMIOS_1_CH[15]_H/LCU0_OUT11/LPSPI0_PCS5/FXIO_D29/LPUART1_DCD_B/EIRQ[14]/ADC0_X[0]/WKPU[25]/CMP2_IN3_A14") (pintype "bidirectional"))
    )
    (net (code "64") (name "unconnected-(U3000B-PTB11{slash}GPIO[43]{slash}LPSPI4_SIN{slash}EMIOS_1_CH[18]_Y{slash}LCU0_OUT8{slash}FXIO_D26{slash}LPI2C0_HREQ{slash}LPUART0_DSR_B{slash}EIRQ[25]{slash}ADC0_X[3]{slash}WKPU[16]{slash}CMP2_IN0-PadC17)") (class "Default")
      (node (ref "U3000") (pin "C17") (pinfunction "PTB11/GPIO[43]/LPSPI4_SIN/EMIOS_1_CH[18]_Y/LCU0_OUT8/FXIO_D26/LPI2C0_HREQ/LPUART0_DSR_B/EIRQ[25]/ADC0_X[3]/WKPU[16]/CMP2_IN0_C17") (pintype "bidirectional"))
    )
    (net (code "65") (name "unconnected-(U3000B-PTB12{slash}GPIO[44]{slash}LPSPI3_PCS3{slash}EMIOS_0_CH[0]_X{slash}LCU0_OUT2{slash}FXIO_D25{slash}LPUART0_DCD_B{slash}LPUART8_RX{slash}EIRQ[26]{slash}WKPU[12]{slash}ADC1_X[1]-PadH17)") (class "Default")
      (node (ref "U3000") (pin "H17") (pinfunction "PTB12/GPIO[44]/LPSPI3_PCS3/EMIOS_0_CH[0]_X/LCU0_OUT2/FXIO_D25/LPUART0_DCD_B/LPUART8_RX/EIRQ[26]/WKPU[12]/ADC1_X[1]_H17") (pintype "bidirectional"))
    )
    (net (code "66") (name "unconnected-(U3000B-PTB13{slash}GPIO[45]{slash}LPSPI3_PCS2{slash}EMIOS_0_CH[1]_G{slash}FXIO_D8{slash}LCU0_OUT3{slash}LPUART8_TX{slash}FXIO_D24{slash}LPUART0_RIN_B{slash}EIRQ[27]{slash}ADC1_S8{slash}ADC2_S8{slash}WKPU[11]{slash}ADC0_S8-PadH16)") (class "Default")
      (node (ref "U3000") (pin "H16") (pinfunction "PTB13/GPIO[45]/LPSPI3_PCS2/EMIOS_0_CH[1]_G/FXIO_D8/LCU0_OUT3/LPUART8_TX/FXIO_D24/LPUART0_RIN_B/EIRQ[27]/ADC1_S8/ADC2_S8/WKPU[11]/ADC0_S8_H16") (pintype "bidirectional"))
    )
    (net (code "67") (name "unconnected-(U3000B-PTB18{slash}GPIO[50]{slash}LPUART13_TX{slash}EMIOS_1_CH[15]_H{slash}FXIO_D1{slash}LPSPI1_PCS1{slash}EMIOS_2_CH[14]_H{slash}TRGMUX_OUT9{slash}GMAC0_MII_RMII_RX_DV_RGMII_RXCTL-PadR1)") (class "Default")
      (node (ref "U3000") (pin "R1") (pinfunction "PTB18/GPIO[50]/LPUART13_TX/EMIOS_1_CH[15]_H/FXIO_D1/LPSPI1_PCS1/EMIOS_2_CH[14]_H/TRGMUX_OUT9/GMAC0_MII_RMII_RX_DV_RGMII_RXCTL_R1") (pintype "bidirectional"))
    )
    (net (code "68") (name "unconnected-(U3000B-PTB19{slash}GPIO[51]{slash}GMAC0_PPS0{slash}EMIOS_1_CH[15]_H{slash}FXIO_D2{slash}GMAC0_MII_RMII_TX_EN{slash}EMIOS_2_CH[15]_H{slash}TRGMUX_OUT10{slash}GMAC1_MII_RMII_RGMII_MDIO{slash}LPUART13_RX{slash}WKPU[38]-PadR2)") (class "Default")
      (node (ref "U3000") (pin "R2") (pinfunction "PTB19/GPIO[51]/GMAC0_PPS0/EMIOS_1_CH[15]_H/FXIO_D2/GMAC0_MII_RMII_TX_EN/EMIOS_2_CH[15]_H/TRGMUX_OUT10/GMAC1_MII_RMII_RGMII_MDIO/LPUART13_RX/WKPU[38]_R2") (pintype "bidirectional"))
    )
    (net (code "69") (name "unconnected-(U3000B-PTB20{slash}GPIO[52]{slash}LPUART14_TX{slash}EMIOS_1_CH[16]_X{slash}FXIO_D3{slash}EMIOS_2_CH[16]_X{slash}TRGMUX_OUT11{slash}GMAC1_PPS2-PadT1)") (class "Default")
      (node (ref "U3000") (pin "T1") (pinfunction "PTB20/GPIO[52]/LPUART14_TX/EMIOS_1_CH[16]_X/FXIO_D3/EMIOS_2_CH[16]_X/TRGMUX_OUT11/GMAC1_PPS2_T1") (pintype "bidirectional"))
    )
    (net (code "70") (name "unconnected-(U3000B-PTB27{slash}GPIO[59]{slash}LPUART5_TX{slash}EMIOS_1_CH[23]_X{slash}FXIO_D8{slash}EMIOS_2_CH[23]_X{slash}LPSPI2_SOUT{slash}SAI0_D0{slash}GMAC1_MII_RMII_RX_ER-PadP9)") (class "Default")
      (node (ref "U3000") (pin "P9") (pinfunction "PTB27/GPIO[59]/LPUART5_TX/EMIOS_1_CH[23]_X/FXIO_D8/EMIOS_2_CH[23]_X/LPSPI2_SOUT/SAI0_D0/GMAC1_MII_RMII_RX_ER_P9") (pintype "bidirectional"))
    )
    (net (code "71") (name "unconnected-(U3000B-PTB30{slash}GPIO[62]{slash}FXIO_D11{slash}HSE_TAMPER_LOOP_OUT0-PadU13)") (class "Default")
      (node (ref "U3000") (pin "U13") (pinfunction "PTB30/GPIO[62]/FXIO_D11/HSE_TAMPER_LOOP_OUT0_U13") (pintype "bidirectional"))
    )
    (net (code "72") (name "unconnected-(U3000B-PTB31{slash}GPIO[63]{slash}EMIOS_0_CH[19]_Y{slash}HSE_TAMPER_EXTIN0{slash}EIRQ[15]-PadT14)") (class "Default")
      (node (ref "U3000") (pin "T14") (pinfunction "PTB31/GPIO[63]/EMIOS_0_CH[19]_Y/HSE_TAMPER_EXTIN0/EIRQ[15]_T14") (pintype "bidirectional"))
    )
  )
)
